# doorbell_modernizr_v3_prog_v0_2.net
KiCad netlist of a schematic drawn in EAGLE
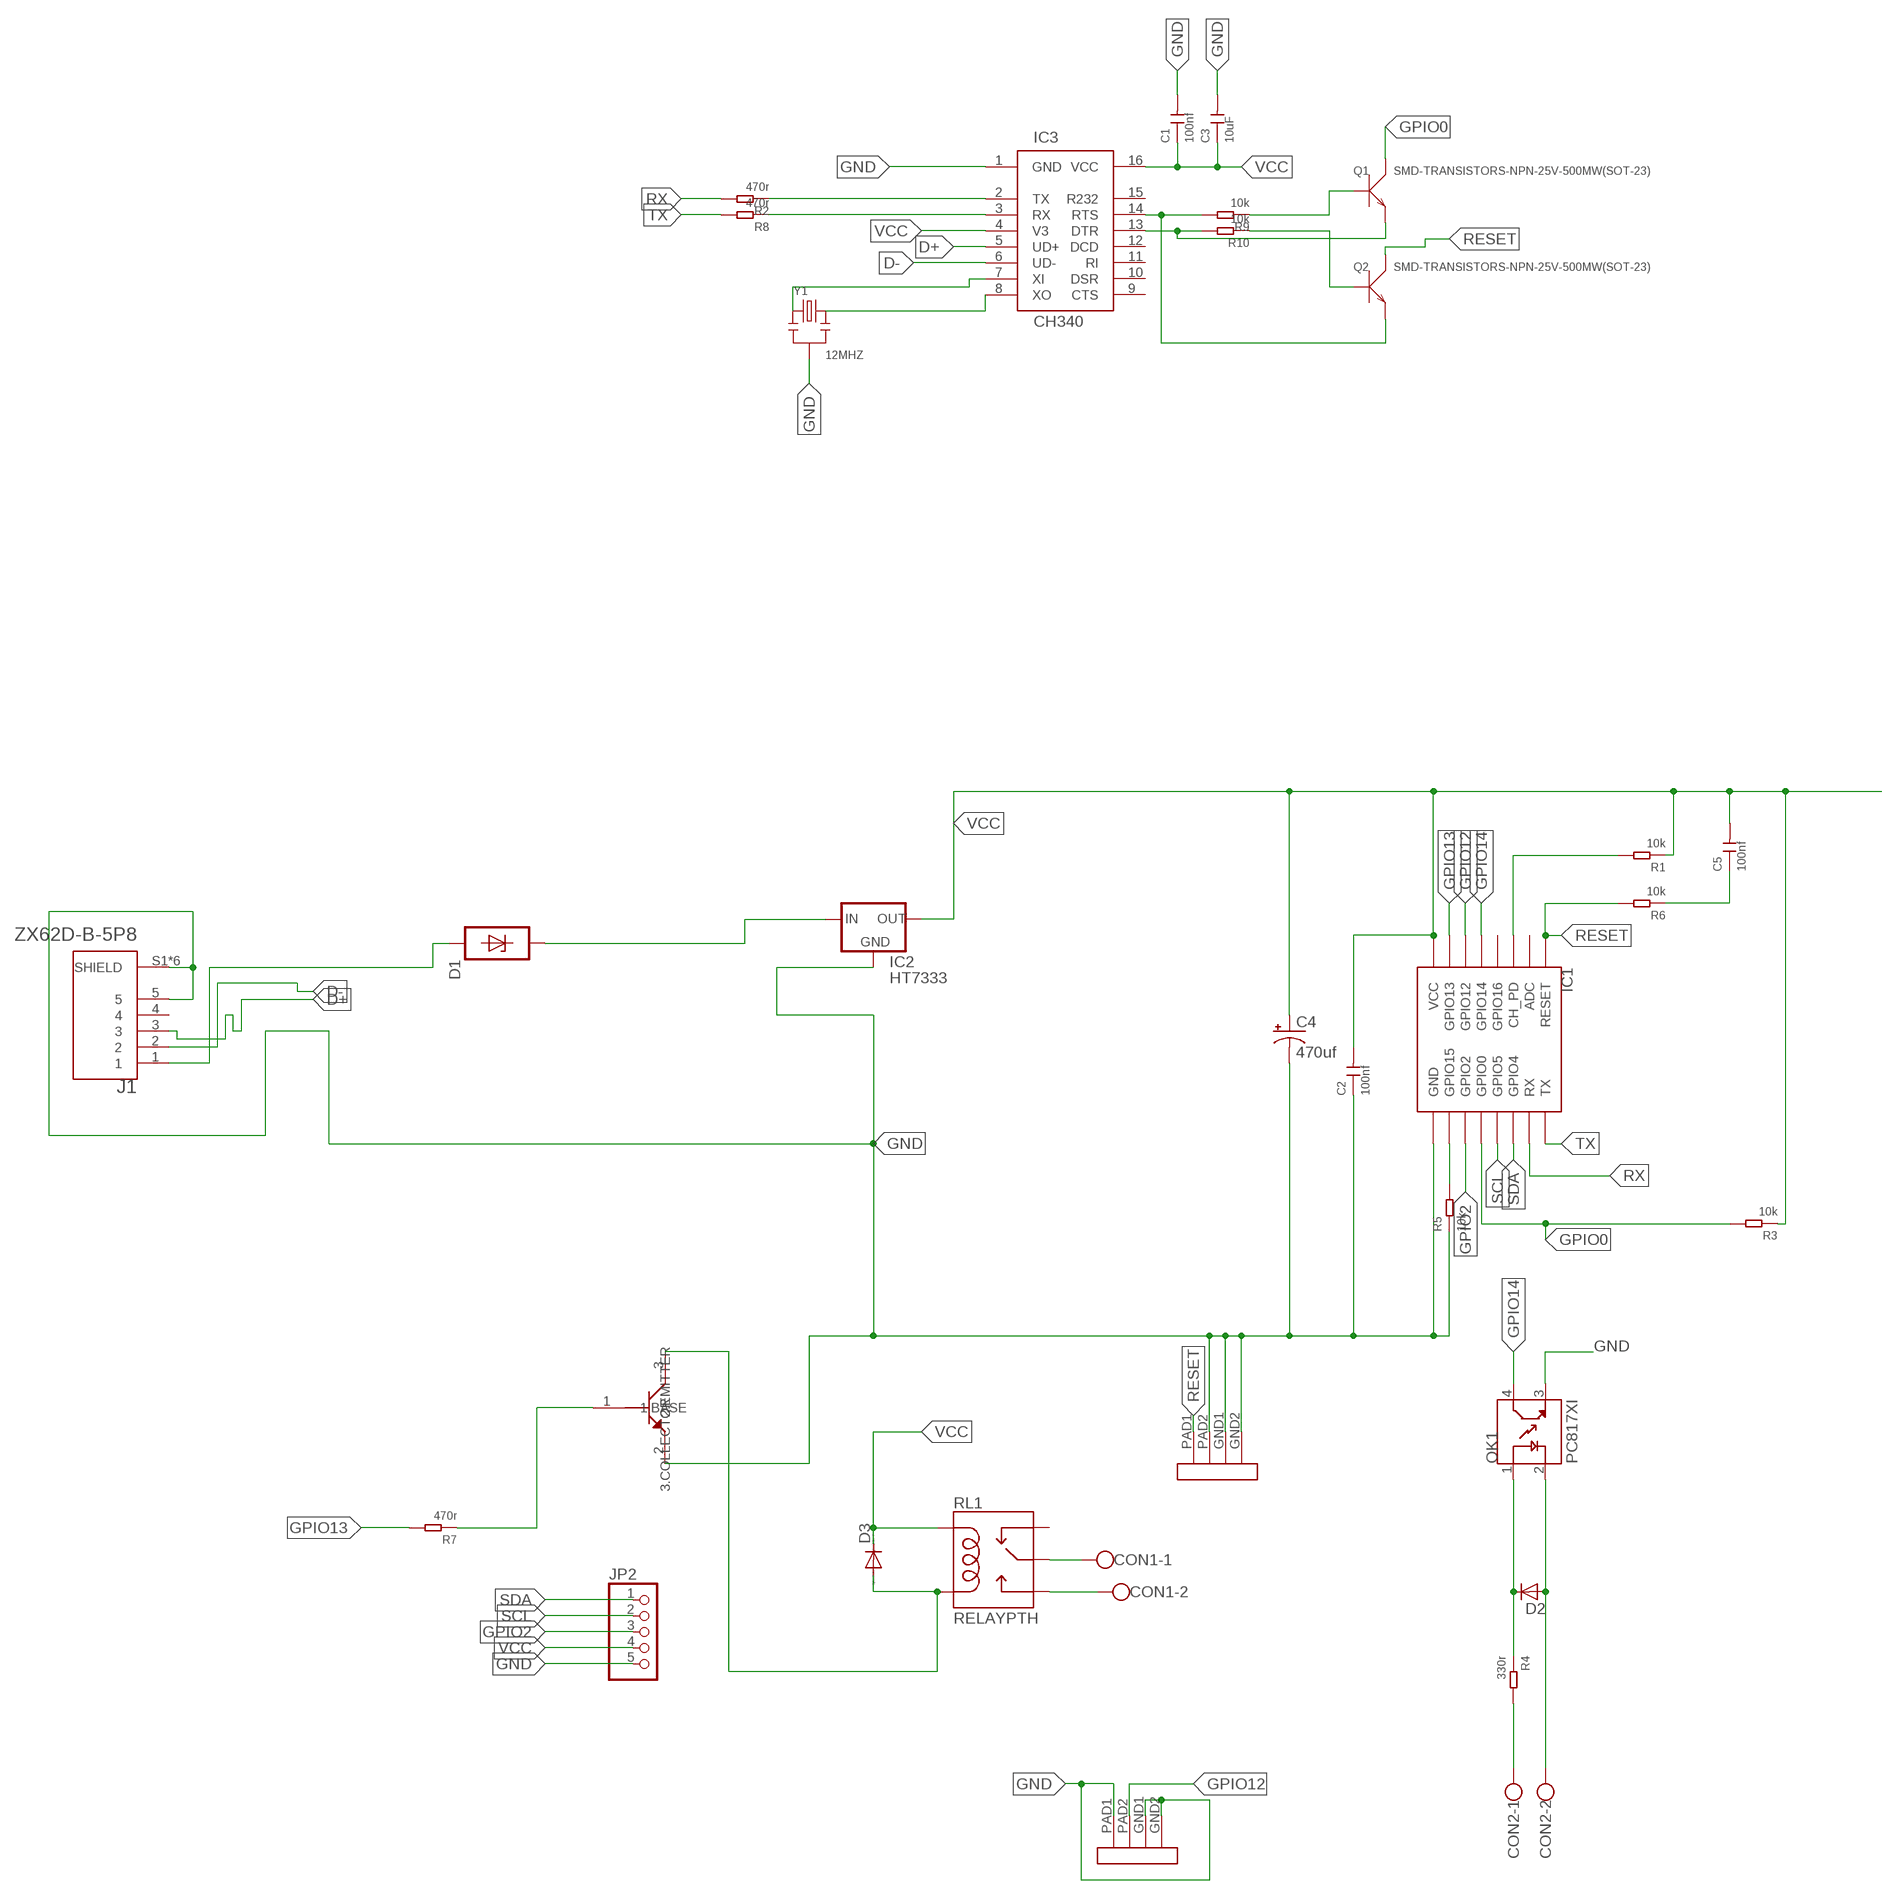
[diagram p0: schematic, sheet 1]

(export (version "E")
  (design (tool "Eeschema 10.0.6"))
  (components
    (comp (ref "C1")
      (value "100nf")
      (footprint "eagle-import:C0603")
      (fields (field (name "MPN") "CC0603KRX7R8BB105"))
      (libsource (lib "eagle-import") (part "CERAMIC-1UF-25V-10%-X7R(0603)"))
    )
    (comp (ref "C2")
      (value "100nf")
      (footprint "eagle-import:C0603")
      (fields (field (name "MPN") "CC0603KRX7R8BB105"))
      (libsource (lib "eagle-import") (part "CERAMIC-1UF-25V-10%-X7R(0603)"))
    )
    (comp (ref "C3")
      (value "10uF")
      (footprint "eagle-import:C0603")
      (fields (field (name "MPN") "CC0603KRX7R8BB105"))
      (libsource (lib "eagle-import") (part "CERAMIC-1UF-25V-10%-X7R(0603)"))
    )
    (comp (ref "C4")
      (value "470uf")
      (footprint "eagle-import:PANASONIC_D")
      (libsource (lib "eagle-import") (part "47UF-50V-20%(ELECT)"))
    )
    (comp (ref "C5")
      (value "100nf")
      (footprint "eagle-import:C0603")
      (fields (field (name "MPN") "CC0603KRX7R8BB105"))
      (libsource (lib "eagle-import") (part "CERAMIC-1UF-25V-10%-X7R(0603)"))
    )
    (comp (ref "CON1")
      (value "W237-102")
      (footprint "eagle-import:W237-102")
      (fields (field (name "MPN") "237-102"))
      (libsource (lib "eagle-import") (part "W237-102"))
    )
    (comp (ref "CON2")
      (value "W237-102")
      (footprint "eagle-import:W237-102")
      (fields (field (name "MPN") "237-102"))
      (libsource (lib "eagle-import") (part "W237-102"))
    )
    (comp (ref "D1")
      (value "SP4020-01FTG")
      (footprint "eagle-import:SOD323")
      (fields (field (name "MF") "Littelfuse"))
      (libsource (lib "eagle-import") (part "SP4020-01FTG"))
    )
    (comp (ref "D2")
      (value "D-SOD123")
      (footprint "eagle-import:SOD123")
      (libsource (lib "eagle-import") (part "D-SOD123"))
    )
    (comp (ref "D3")
      (value "DIODE-SOD123")
      (footprint "eagle-import:SOD123")
      (libsource (lib "eagle-import") (part "DIODE-SOD123"))
    )
    (comp (ref "IC1")
      (value "ESP12SMD")
      (footprint "eagle-import:ESP12-SMD")
      (libsource (lib "eagle-import") (part "ESP12SMD"))
    )
    (comp (ref "IC2")
      (value "HT7333")
      (footprint "eagle-import:SOT-89")
      (libsource (lib "eagle-import") (part "HT7333"))
    )
    (comp (ref "IC3")
      (value "CH340")
      (footprint "eagle-import:SOIC16")
      (fields (field (name "MF") "DFRobot"))
      (libsource (lib "eagle-import") (part "CH340"))
    )
    (comp (ref "J1")
      (value "ZX62D-B-5P8")
      (footprint "eagle-import:HRS_ZX62D-B-5P8")
      (fields (field (name "MF") "Hirose"))
      (libsource (lib "eagle-import") (part "ZX62D-B-5P8"))
    )
    (comp (ref "JP2")
      (value "PINHD-1X5")
      (footprint "eagle-import:1X05")
      (libsource (lib "eagle-import") (part "PINHD-1X5"))
    )
    (comp (ref "OK1")
      (value "PC817XI")
      (footprint "eagle-import:SOIC254P975X460-4N")
      (fields (field (name "MF") "Sharp Microelectronics"))
      (libsource (lib "eagle-import") (part "PC817XI"))
    )
    (comp (ref "Q1")
      (value "SMD-TRANSISTORS-NPN-25V-500MW(SOT-23)")
      (footprint "eagle-import:SOT-23")
      (fields (field (name "MF") "Recom Power") (field (name "MP") "S8050"))
      (libsource (lib "eagle-import") (part "SMD-TRANSISTORS-NPN-25V-500MW(SOT-23)"))
    )
    (comp (ref "Q2")
      (value "SMD-TRANSISTORS-NPN-25V-500MW(SOT-23)")
      (footprint "eagle-import:SOT-23")
      (fields (field (name "MF") "Recom Power") (field (name "MP") "S8050"))
      (libsource (lib "eagle-import") (part "SMD-TRANSISTORS-NPN-25V-500MW(SOT-23)"))
    )
    (comp (ref "Q3")
      (value "2N2222")
      (footprint "eagle-import:SOT23")
      (fields (field (name "MF") "MAXIM") (field (name "MPN") "MAX6520EUR-T"))
      (libsource (lib "eagle-import") (part "2N2222"))
    )
    (comp (ref "R1")
      (value "10k")
      (footprint "eagle-import:R0603")
      (fields (field (name "MPN") "RC0603JR-0739RL"))
      (libsource (lib "eagle-import") (part "SMD-RES-39R-5%-1/10W(0603)"))
    )
    (comp (ref "R2")
      (value "470r")
      (footprint "eagle-import:R0603")
      (fields (field (name "MPN") "RC0603JR-0739RL"))
      (libsource (lib "eagle-import") (part "SMD-RES-39R-5%-1/10W(0603)"))
    )
    (comp (ref "R3")
      (value "10k")
      (footprint "eagle-import:R0603")
      (fields (field (name "MPN") "RC0603JR-0739RL"))
      (libsource (lib "eagle-import") (part "SMD-RES-39R-5%-1/10W(0603)"))
    )
    (comp (ref "R4")
      (value "330r")
      (footprint "eagle-import:R0603")
      (fields (field (name "MPN") "RC0603JR-0739RL"))
      (libsource (lib "eagle-import") (part "SMD-RES-39R-5%-1/10W(0603)"))
    )
    (comp (ref "R5")
      (value "10k")
      (footprint "eagle-import:R0603")
      (fields (field (name "MPN") "RC0603JR-0739RL"))
      (libsource (lib "eagle-import") (part "SMD-RES-39R-5%-1/10W(0603)"))
    )
    (comp (ref "R6")
      (value "10k")
      (footprint "eagle-import:R0603")
      (fields (field (name "MPN") "RC0603JR-0739RL"))
      (libsource (lib "eagle-import") (part "SMD-RES-39R-5%-1/10W(0603)"))
    )
    (comp (ref "R7")
      (value "470r")
      (footprint "eagle-import:R0603")
      (fields (field (name "MPN") "RC0603JR-0739RL"))
      (libsource (lib "eagle-import") (part "SMD-RES-39R-5%-1/10W(0603)"))
    )
    (comp (ref "R8")
      (value "470r")
      (footprint "eagle-import:R0603")
      (fields (field (name "MPN") "RC0603JR-0739RL"))
      (libsource (lib "eagle-import") (part "SMD-RES-39R-5%-1/10W(0603)"))
    )
    (comp (ref "R9")
      (value "10k")
      (footprint "eagle-import:R0603")
      (fields (field (name "MPN") "RC0603JR-0739RL"))
      (libsource (lib "eagle-import") (part "SMD-RES-39R-5%-1/10W(0603)"))
    )
    (comp (ref "R10")
      (value "10k")
      (footprint "eagle-import:R0603")
      (fields (field (name "MPN") "RC0603JR-0739RL"))
      (libsource (lib "eagle-import") (part "SMD-RES-39R-5%-1/10W(0603)"))
    )
    (comp (ref "RL1")
      (value "RELAYPTH")
      (footprint "eagle-import:SRD-05VDC-SL-C")
      (libsource (lib "eagle-import") (part "RELAYPTH"))
    )
    (comp (ref "SW1")
      (value "MINI-SIDE-SWITCH")
      (footprint "eagle-import:MINI-SIDE-SWITCH")
      (libsource (lib "eagle-import") (part "MINI-SIDE-SWITCH"))
    )
    (comp (ref "SW2")
      (value "MINI-SIDE-SWITCH")
      (footprint "eagle-import:MINI-SIDE-SWITCH")
      (libsource (lib "eagle-import") (part "MINI-SIDE-SWITCH"))
    )
    (comp (ref "Y1")
      (value "12MHZ")
      (footprint "eagle-import:X3-SMD-3.6X1.3X0.8MM")
      (fields (field (name "MPN") "CSTCE8M00G15L99-R0"))
      (libsource (lib "eagle-import") (part "SMD-RESONATOR-8MHZ-33PF-0.1%(3P-3.2X1.3MM)"))
    )
  )
  (nets
    (net (code "1") (name "D+") (class "Default")
      (node (ref "IC3") (pin "5") (pinfunction "UD+_5") (pintype "bidirectional"))
      (node (ref "J1") (pin "3") (pinfunction "3_3") (pintype "passive"))
    )
    (net (code "2") (name "D-") (class "Default")
      (node (ref "IC3") (pin "6") (pinfunction "UD-_6") (pintype "bidirectional"))
      (node (ref "J1") (pin "2") (pinfunction "2_2") (pintype "passive"))
    )
    (net (code "3") (name "GND") (class "Default")
      (node (ref "C1") (pin "2") (pinfunction "2_2") (pintype "passive"))
      (node (ref "C2") (pin "1") (pinfunction "1_1") (pintype "passive"))
      (node (ref "C3") (pin "2") (pinfunction "2_2") (pintype "passive"))
      (node (ref "C4") (pin "-") (pinfunction "-_-") (pintype "passive"))
      (node (ref "IC1") (pin "GND") (pinfunction "GND_GND") (pintype "bidirectional"))
      (node (ref "IC2") (pin "2") (pinfunction "GND_2") (pintype "input"))
      (node (ref "IC3") (pin "1") (pinfunction "GND_1") (pintype "power_in"))
      (node (ref "J1") (pin "5") (pinfunction "5_5") (pintype "passive"))
      (node (ref "J1") (pin "S1") (pinfunction "SHIELD_S1") (pintype "passive"))
      (node (ref "J1") (pin "S2") (pinfunction "SHIELD_S2") (pintype "passive"))
      (node (ref "J1") (pin "S3") (pinfunction "SHIELD_S3") (pintype "passive"))
      (node (ref "J1") (pin "S4") (pinfunction "SHIELD_S4") (pintype "passive"))
      (node (ref "J1") (pin "S5") (pinfunction "SHIELD_S5") (pintype "passive"))
      (node (ref "J1") (pin "S6") (pinfunction "SHIELD_S6") (pintype "passive"))
      (node (ref "JP2") (pin "5") (pinfunction "5_5") (pintype "passive"))
      (node (ref "OK1") (pin "3") (pinfunction "ET_3") (pintype "passive"))
      (node (ref "Q3") (pin "2") (pinfunction "2.EMITTER_2") (pintype "bidirectional"))
      (node (ref "R5") (pin "1") (pinfunction "1_1") (pintype "passive"))
      (node (ref "SW1") (pin "GND1") (pinfunction "GND1_GND1") (pintype "passive"))
      (node (ref "SW1") (pin "GND2") (pinfunction "GND2_GND2") (pintype "passive"))
      (node (ref "SW1") (pin "PAD2") (pinfunction "PAD2_PAD2") (pintype "passive"))
      (node (ref "SW2") (pin "GND1") (pinfunction "GND1_GND1") (pintype "passive"))
      (node (ref "SW2") (pin "GND2") (pinfunction "GND2_GND2") (pintype "passive"))
      (node (ref "SW2") (pin "PAD1") (pinfunction "PAD1_PAD1") (pintype "passive"))
      (node (ref "Y1") (pin "2") (pinfunction "2_2") (pintype "passive"))
    )
    (net (code "4") (name "GPIO0") (class "Default")
      (node (ref "IC1") (pin "GPIO0") (pinfunction "GPIO0_GPIO0") (pintype "bidirectional"))
      (node (ref "Q1") (pin "3") (pinfunction "C_3") (pintype "passive"))
      (node (ref "R3") (pin "2") (pinfunction "2_2") (pintype "passive"))
    )
    (net (code "5") (name "GPIO2") (class "Default")
      (node (ref "IC1") (pin "GPIO2") (pinfunction "GPIO2_GPIO2") (pintype "bidirectional"))
      (node (ref "JP2") (pin "3") (pinfunction "3_3") (pintype "passive"))
    )
    (net (code "6") (name "GPIO12") (class "Default")
      (node (ref "IC1") (pin "GPIO12") (pinfunction "GPIO12_GPIO12") (pintype "bidirectional"))
      (node (ref "SW2") (pin "PAD2") (pinfunction "PAD2_PAD2") (pintype "passive"))
    )
    (net (code "7") (name "GPIO13") (class "Default")
      (node (ref "IC1") (pin "GPIO13") (pinfunction "GPIO13_GPIO13") (pintype "bidirectional"))
      (node (ref "R7") (pin "2") (pinfunction "2_2") (pintype "passive"))
    )
    (net (code "8") (name "GPIO14") (class "Default")
      (node (ref "IC1") (pin "GPIO14") (pinfunction "GPIO14_GPIO14") (pintype "bidirectional"))
      (node (ref "OK1") (pin "4") (pinfunction "CT_4") (pintype "passive"))
    )
    (net (code "9") (name "Net-(C5-Pad1)") (class "Default")
      (node (ref "C5") (pin "1") (pinfunction "1_1") (pintype "passive"))
      (node (ref "R6") (pin "1") (pinfunction "1_1") (pintype "passive"))
    )
    (net (code "10") (name "Net-(CON1A-KL)") (class "Default")
      (node (ref "CON1") (pin "1") (pinfunction "KL_1") (pintype "passive"))
      (node (ref "RL1") (pin "SWCOMMON") (pinfunction "SWCOMMON_SWCOMMON") (pintype "bidirectional"))
    )
    (net (code "11") (name "Net-(CON1B-KL)") (class "Default")
      (node (ref "CON1") (pin "2") (pinfunction "KL_2") (pintype "passive"))
      (node (ref "RL1") (pin "SWOPEN") (pinfunction "SWOPEN_SWOPEN") (pintype "bidirectional"))
    )
    (net (code "12") (name "Net-(CON2A-KL)") (class "Default")
      (node (ref "CON2") (pin "1") (pinfunction "KL_1") (pintype "passive"))
      (node (ref "R4") (pin "2") (pinfunction "2_2") (pintype "passive"))
    )
    (net (code "13") (name "Net-(CON2B-KL)") (class "Default")
      (node (ref "CON2") (pin "2") (pinfunction "KL_2") (pintype "passive"))
      (node (ref "D2") (pin "2") (pinfunction "A_2") (pintype "passive"))
      (node (ref "OK1") (pin "2") (pinfunction "C_2") (pintype "passive"))
    )
    (net (code "14") (name "Net-(D1-Pad1)") (class "Default")
      (node (ref "D1") (pin "1") (pinfunction "1_1") (pintype "passive"))
      (node (ref "IC2") (pin "4") (pinfunction "IN_4") (pintype "input"))
      (node (ref "IC2") (pin "P$2") (pinfunction "IN_P$2") (pintype "input"))
    )
    (net (code "15") (name "Net-(D1-Pad2)") (class "Default")
      (node (ref "D1") (pin "2") (pinfunction "2_2") (pintype "passive"))
      (node (ref "J1") (pin "1") (pinfunction "1_1") (pintype "passive"))
    )
    (net (code "16") (name "Net-(D2-C)") (class "Default")
      (node (ref "D2") (pin "1") (pinfunction "C_1") (pintype "passive"))
      (node (ref "OK1") (pin "1") (pinfunction "A_1") (pintype "passive"))
      (node (ref "R4") (pin "1") (pinfunction "1_1") (pintype "passive"))
    )
    (net (code "17") (name "Net-(IC1-PadCH_PD)") (class "Default")
      (node (ref "IC1") (pin "CH_PD") (pinfunction "CH_PD_CH_PD") (pintype "bidirectional"))
      (node (ref "R1") (pin "2") (pinfunction "2_2") (pintype "passive"))
    )
    (net (code "18") (name "Net-(IC1-PadGPIO15)") (class "Default")
      (node (ref "IC1") (pin "GPIO15") (pinfunction "GPIO15_GPIO15") (pintype "bidirectional"))
      (node (ref "R5") (pin "2") (pinfunction "2_2") (pintype "passive"))
    )
    (net (code "19") (name "Net-(IC3-DTR)") (class "Default")
      (node (ref "IC3") (pin "13") (pinfunction "DTR_13") (pintype "bidirectional"))
      (node (ref "Q1") (pin "2") (pinfunction "E_2") (pintype "passive"))
      (node (ref "R10") (pin "2") (pinfunction "2_2") (pintype "passive"))
    )
    (net (code "20") (name "Net-(IC3-RTS)") (class "Default")
      (node (ref "IC3") (pin "14") (pinfunction "RTS_14") (pintype "bidirectional"))
      (node (ref "Q2") (pin "2") (pinfunction "E_2") (pintype "passive"))
      (node (ref "R9") (pin "2") (pinfunction "2_2") (pintype "passive"))
    )
    (net (code "21") (name "Net-(IC3-RX)") (class "Default")
      (node (ref "IC3") (pin "3") (pinfunction "RX_3") (pintype "input"))
      (node (ref "R8") (pin "1") (pinfunction "1_1") (pintype "passive"))
    )
    (net (code "22") (name "Net-(IC3-TX)") (class "Default")
      (node (ref "IC3") (pin "2") (pinfunction "TX_2") (pintype "output"))
      (node (ref "R2") (pin "1") (pinfunction "1_1") (pintype "passive"))
    )
    (net (code "23") (name "Net-(IC3-XI)") (class "Default")
      (node (ref "IC3") (pin "7") (pinfunction "XI_7") (pintype "input"))
      (node (ref "Y1") (pin "1") (pinfunction "1_1") (pintype "passive"))
    )
    (net (code "24") (name "Net-(IC3-XO)") (class "Default")
      (node (ref "IC3") (pin "8") (pinfunction "XO_8") (pintype "output"))
      (node (ref "Y1") (pin "3") (pinfunction "3_3") (pintype "passive"))
    )
    (net (code "25") (name "Net-(Q1-B)") (class "Default")
      (node (ref "Q1") (pin "1") (pinfunction "B_1") (pintype "passive"))
      (node (ref "R9") (pin "1") (pinfunction "1_1") (pintype "passive"))
    )
    (net (code "26") (name "Net-(Q2-B)") (class "Default")
      (node (ref "Q2") (pin "1") (pinfunction "B_1") (pintype "passive"))
      (node (ref "R10") (pin "1") (pinfunction "1_1") (pintype "passive"))
    )
    (net (code "27") (name "Net-(Q3-1.BASE)") (class "Default")
      (node (ref "Q3") (pin "1") (pinfunction "1.BASE_1") (pintype "bidirectional"))
      (node (ref "R7") (pin "1") (pinfunction "1_1") (pintype "passive"))
    )
    (net (code "28") (name "Net-(Q3-3.COLLECTOR)") (class "Default")
      (node (ref "D3") (pin "A") (pinfunction "A_A") (pintype "passive"))
      (node (ref "Q3") (pin "3") (pinfunction "3.COLLECTOR_3") (pintype "bidirectional"))
      (node (ref "RL1") (pin "COIL0") (pinfunction "COIL0_COIL0") (pintype "bidirectional"))
    )
    (net (code "29") (name "RESET") (class "Default")
      (node (ref "IC1") (pin "RESET") (pinfunction "RESET_RESET") (pintype "bidirectional"))
      (node (ref "Q2") (pin "3") (pinfunction "C_3") (pintype "passive"))
      (node (ref "R6") (pin "2") (pinfunction "2_2") (pintype "passive"))
      (node (ref "SW1") (pin "PAD1") (pinfunction "PAD1_PAD1") (pintype "passive"))
    )
    (net (code "30") (name "RX") (class "Default")
      (node (ref "IC1") (pin "RXD0") (pinfunction "RX_RXD0") (pintype "bidirectional"))
      (node (ref "R2") (pin "2") (pinfunction "2_2") (pintype "passive"))
    )
    (net (code "31") (name "SCL") (class "Default")
      (node (ref "IC1") (pin "GPIO5") (pinfunction "GPIO5_GPIO5") (pintype "bidirectional"))
      (node (ref "JP2") (pin "2") (pinfunction "2_2") (pintype "passive"))
    )
    (net (code "32") (name "SDA") (class "Default")
      (node (ref "IC1") (pin "GPIO4") (pinfunction "GPIO4_GPIO4") (pintype "bidirectional"))
      (node (ref "JP2") (pin "1") (pinfunction "1_1") (pintype "passive"))
    )
    (net (code "33") (name "TX") (class "Default")
      (node (ref "IC1") (pin "TXD0") (pinfunction "TX_TXD0") (pintype "bidirectional"))
      (node (ref "R8") (pin "2") (pinfunction "2_2") (pintype "passive"))
    )
    (net (code "34") (name "VCC") (class "Default")
      (node (ref "C1") (pin "1") (pinfunction "1_1") (pintype "passive"))
      (node (ref "C2") (pin "2") (pinfunction "2_2") (pintype "passive"))
      (node (ref "C3") (pin "1") (pinfunction "1_1") (pintype "passive"))
      (node (ref "C4") (pin "+") (pinfunction "+_+") (pintype "passive"))
      (node (ref "C5") (pin "2") (pinfunction "2_2") (pintype "passive"))
      (node (ref "D3") (pin "C") (pinfunction "C_C") (pintype "passive"))
      (node (ref "IC1") (pin "VCC") (pinfunction "VCC_VCC") (pintype "bidirectional"))
      (node (ref "IC2") (pin "1") (pinfunction "OUT_1") (pintype "passive"))
      (node (ref "IC3") (pin "16") (pinfunction "VCC_16") (pintype "power_in"))
      (node (ref "IC3") (pin "4") (pinfunction "V3_4") (pintype "power_in"))
      (node (ref "JP2") (pin "4") (pinfunction "4_4") (pintype "passive"))
      (node (ref "R1") (pin "1") (pinfunction "1_1") (pintype "passive"))
      (node (ref "R3") (pin "1") (pinfunction "1_1") (pintype "passive"))
      (node (ref "RL1") (pin "COIL1") (pinfunction "COIL1_COIL1") (pintype "bidirectional"))
    )
    (net (code "35") (name "unconnected-(IC1-PadADC)") (class "Default")
      (node (ref "IC1") (pin "ADC") (pinfunction "ADC_ADC") (pintype "bidirectional"))
    )
    (net (code "36") (name "unconnected-(IC1-PadGPIO16)") (class "Default")
      (node (ref "IC1") (pin "GPIO16") (pinfunction "GPIO16_GPIO16") (pintype "bidirectional"))
    )
    (net (code "37") (name "unconnected-(IC3-CTS-Pad9)") (class "Default")
      (node (ref "IC3") (pin "9") (pinfunction "CTS_9") (pintype "bidirectional"))
    )
    (net (code "38") (name "unconnected-(IC3-DCD-Pad12)") (class "Default")
      (node (ref "IC3") (pin "12") (pinfunction "DCD_12") (pintype "bidirectional"))
    )
    (net (code "39") (name "unconnected-(IC3-DSR-Pad10)") (class "Default")
      (node (ref "IC3") (pin "10") (pinfunction "DSR_10") (pintype "bidirectional"))
    )
    (net (code "40") (name "unconnected-(IC3-R232-Pad15)") (class "Default")
      (node (ref "IC3") (pin "15") (pinfunction "R232_15") (pintype "bidirectional"))
    )
    (net (code "41") (name "unconnected-(IC3-RI-Pad11)") (class "Default")
      (node (ref "IC3") (pin "11") (pinfunction "RI_11") (pintype "bidirectional"))
    )
    (net (code "42") (name "unconnected-(J1-Pad4)") (class "Default")
      (node (ref "J1") (pin "4") (pinfunction "4_4") (pintype "passive"))
    )
    (net (code "43") (name "unconnected-(RL1-SWCLOSE-PadSWCLOSED)") (class "Default")
      (node (ref "RL1") (pin "SWCLOSED") (pinfunction "SWCLOSE_SWCLOSED") (pintype "bidirectional"))
    )
  )
)
